# design.net
KiCad netlist of a schematic drawn in EasyEDA Pro
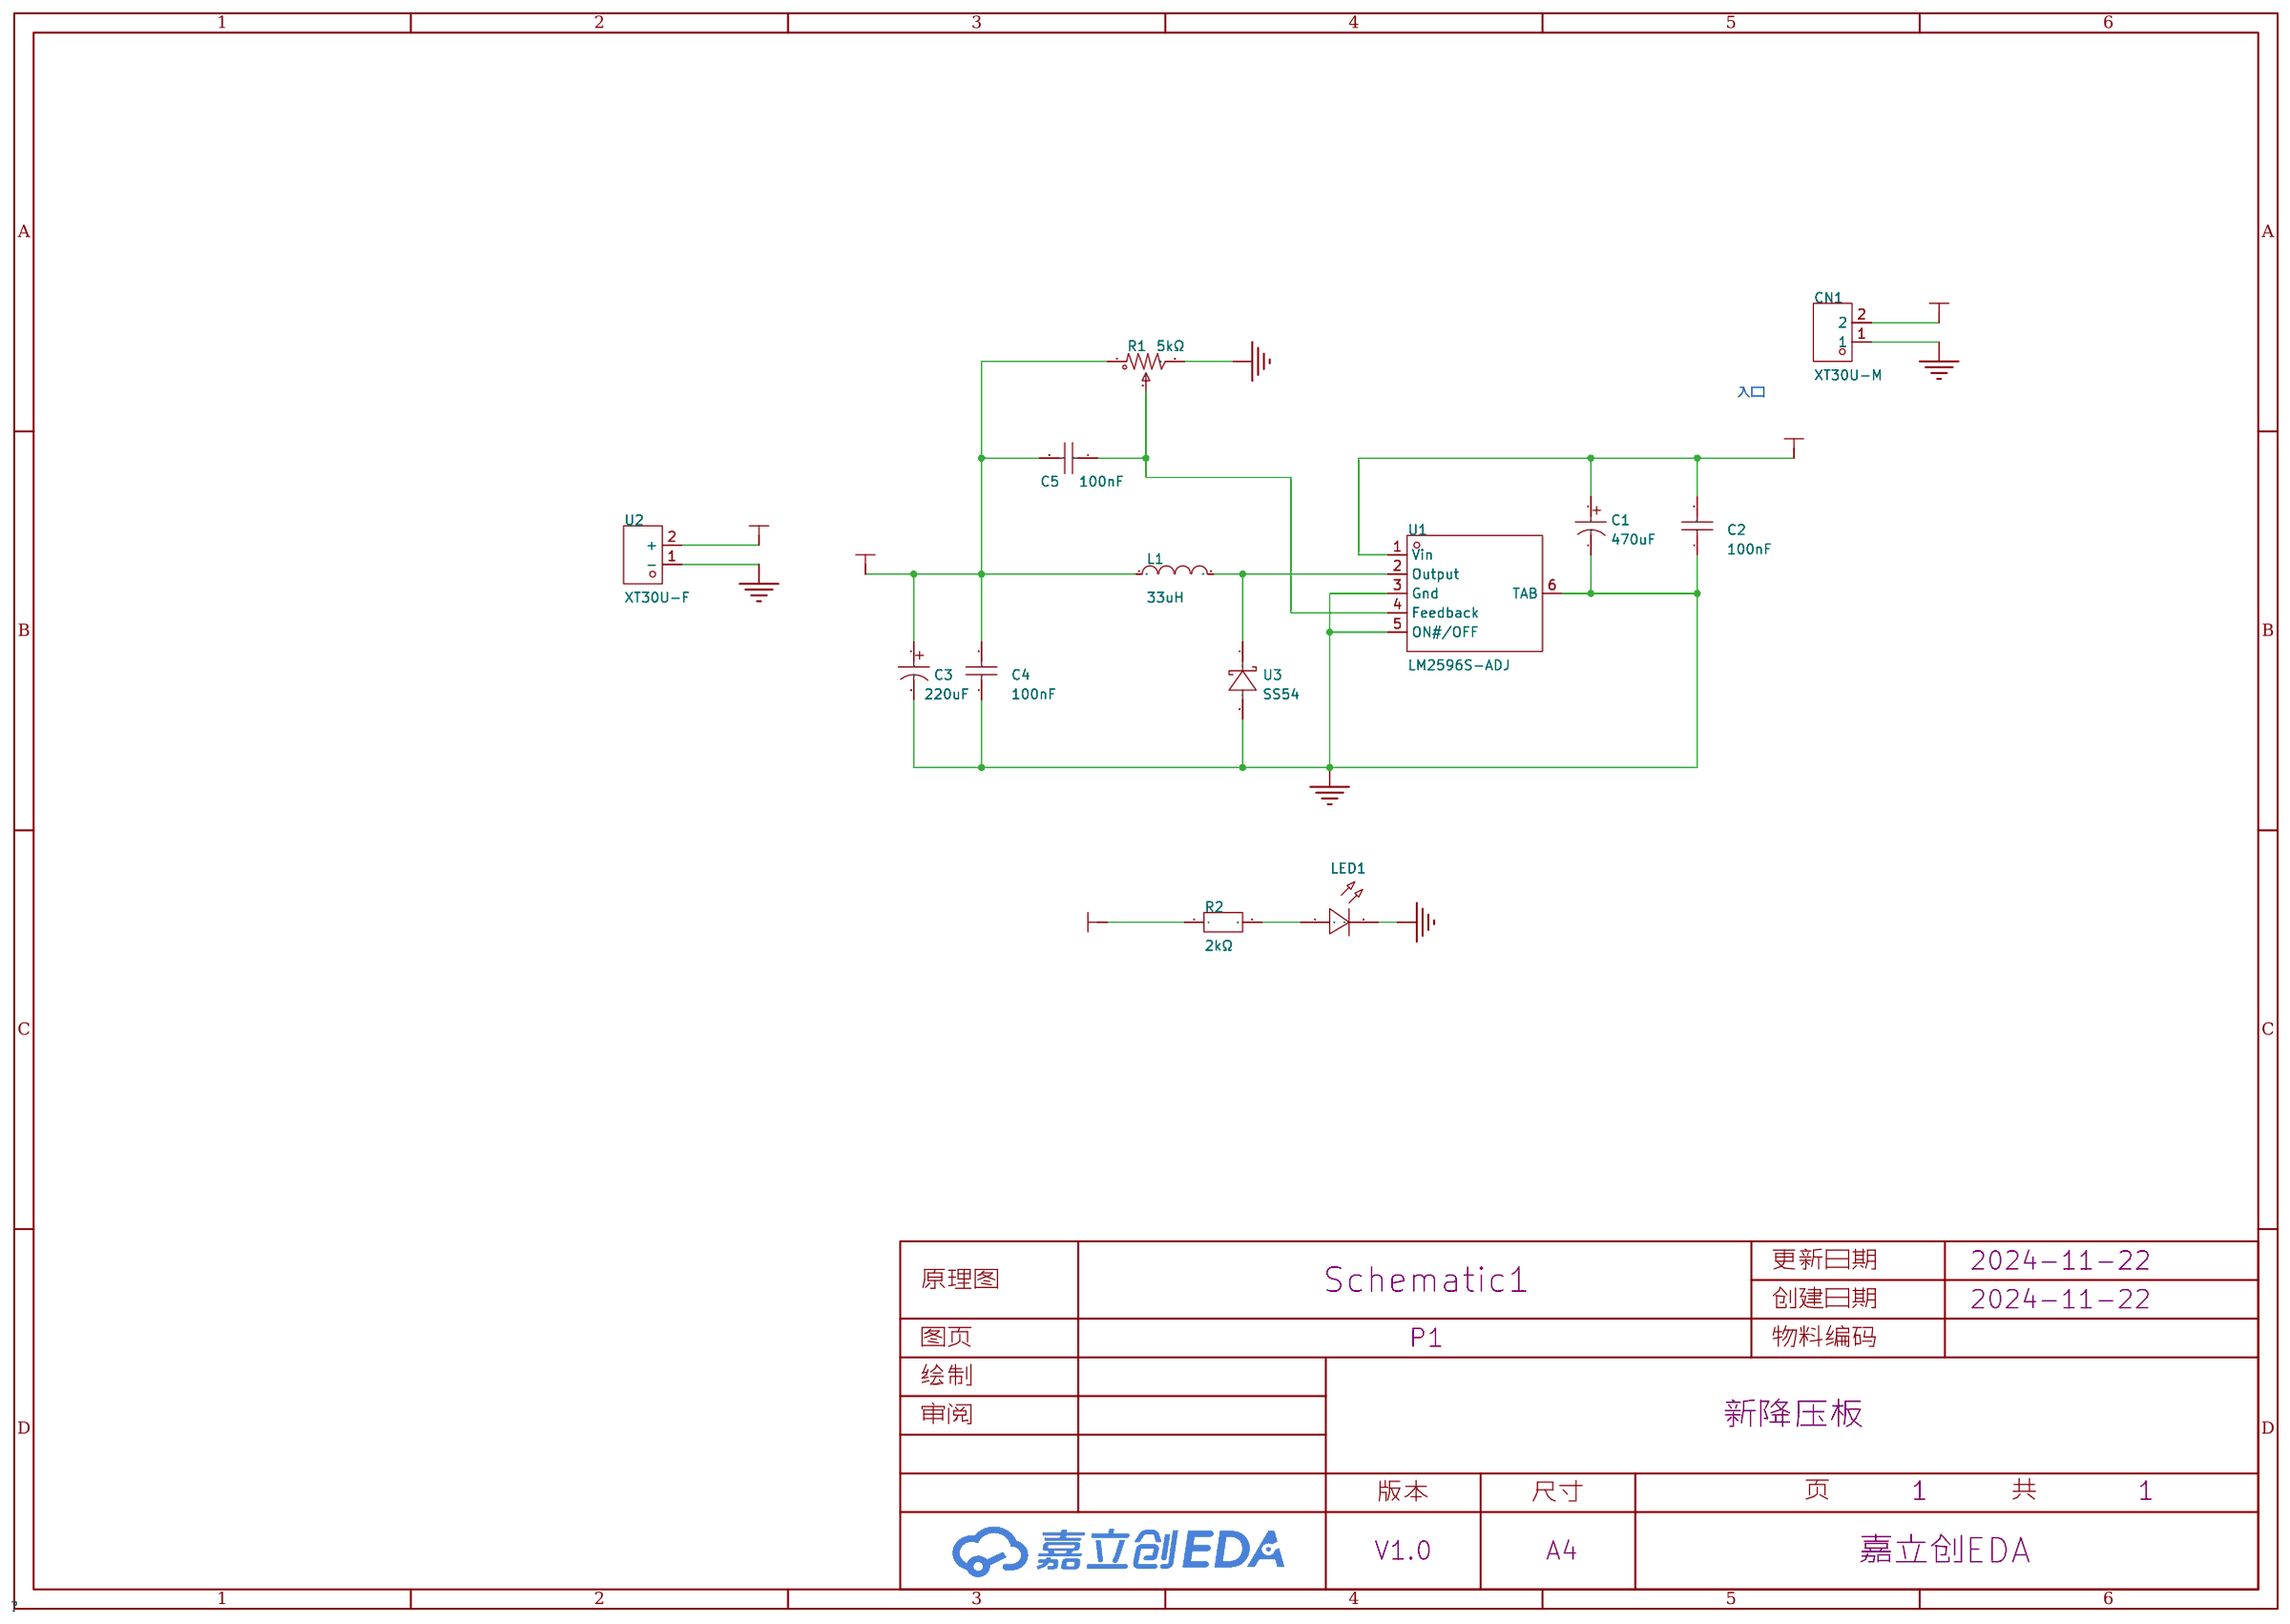
[diagram p0: schematic sheet]

(export (version "E")
  (design (tool "Eeschema 10.0.6"))
  (components
    (comp (ref "C1")
      (value "470uF")
      (footprint "easyedapro:CAP-SMD_BD8.0-L8.3-W8.3-FD")
      (description "容值:470uF;精度:±20%;额定电压:16V;纹波电流:450mA@120Hz;等效串联电阻:430mΩ;")
      (fields (field (name "Manufacturer Part") "RVE1C471M0810") (field (name "Manufacturer") "ROQANG(容强)"))
      (libsource (lib "easyedapro") (part "RVE1C471M0810"))
    )
    (comp (ref "C2")
      (value "100nF")
      (footprint "easyedapro:C0805")
      (description "容值:100nF;精度:±10%;额定电压:50V;材质(温度系数):X7R;")
      (fields
        (field (name "Manufacturer Part") "CL21B104KBCNNNC")
        (field (name "Manufacturer") "SAMSUNG(三星)")
      )
      (libsource (lib "easyedapro") (part "CL21B104KBCNNNC"))
    )
    (comp (ref "C3")
      (value "220uF")
      (footprint "easyedapro:CAP-SMD_BD6.3-L6.6-W6.6-FD")
      (description "容值:220uF;精度:±20%;额定电压:16V;纹波电流:110mA@120Hz;等效串联电阻:-;")
      (fields (field (name "Manufacturer Part") "VT1C221M0607") (field (name "Manufacturer") "ROQANG(容强)"))
      (libsource (lib "easyedapro") (part "VT1C221M0607"))
    )
    (comp (ref "C4")
      (value "100nF")
      (footprint "easyedapro:C0805")
      (description "容值:100nF;精度:±10%;额定电压:50V;材质(温度系数):X7R;")
      (fields
        (field (name "Manufacturer Part") "CL21B104KBCNNNC")
        (field (name "Manufacturer") "SAMSUNG(三星)")
      )
      (libsource (lib "easyedapro") (part "CL21B104KBCNNNC"))
    )
    (comp (ref "C5")
      (value "100nF")
      (footprint "easyedapro:C0805")
      (description "容值:100nF;精度:±10%;额定电压:50V;材质(温度系数):X7R;")
      (fields
        (field (name "Manufacturer Part") "CL21B104KBCNNNC")
        (field (name "Manufacturer") "SAMSUNG(三星)")
      )
      (libsource (lib "easyedapro") (part "CL21B104KBCNNNC"))
    )
    (comp (ref "CN1")
      (value "XT30U-M")
      (footprint "easyedapro:CONN-TH_XT30U-M")
      (description "类别:-;类型1:-;")
      (fields (field (name "Manufacturer") "AMASS(艾迈斯)"))
      (libsource (lib "easyedapro") (part "XT30U-M"))
    )
    (comp (ref "L1")
      (value "33uH")
      (footprint "easyedapro:IND-SMD_L12.0-W12.0")
      (description "电感值:33uH;精度:±20%;额定电流:3A;")
      (fields
        (field (name "Manufacturer Part") "SLH1207S330MTT")
        (field (name "Manufacturer") "Sunltech(韩国顺磁)")
      )
      (libsource (lib "easyedapro") (part "SLH1207S330MTT"))
    )
    (comp (ref "LED1")
      (value "~")
      (footprint "easyedapro:LED-TH_5mm")
      (libsource (lib "easyedapro") (part "LED_TH-R"))
    )
    (comp (ref "R1")
      (value "5kΩ")
      (footprint "easyedapro:RES-ADJ-TH_3P-L9.5-W4.85-P2.50-BL-BS")
      (description "阻值:5kΩ;精度:±10%;")
      (fields (field (name "Manufacturer Part") "3296W-1-502") (field (name "Manufacturer") "BOCHEN(博晨)"))
      (libsource (lib "easyedapro") (part "3296W-1-502"))
    )
    (comp (ref "R2")
      (value "2kΩ")
      (footprint "easyedapro:R0603")
      (description "阻值:2kΩ;精度:±1%;功率:-;温度系数:±100ppm/°C;")
      (fields
        (field (name "Manufacturer Part") "SC0603F2001F2BNRH")
        (field (name "Manufacturer") "Sunway(信维通信)")
      )
      (libsource (lib "easyedapro") (part "SC0603F2001F2BNRH"))
    )
    (comp (ref "U1")
      (value "LM2596S-ADJ")
      (footprint "easyedapro:TO-263-5_L10.2-W8.9-P1.70-BR")
      (description "功能类型:降压型;输出类型:可调;输入电压:40V;输出电压:1.2V~37V;输出电流:3A;")
      (fields (field (name "Manufacturer") "UMW(友台半导体)"))
      (libsource (lib "easyedapro") (part "LM2596S-ADJ"))
    )
    (comp (ref "U2")
      (value "XT30U-F")
      (footprint "easyedapro:CONN-TH_XT30U-F")
      (description "类别:-;类型1:-;")
      (fields (field (name "Manufacturer") "AMASS(艾迈斯)"))
      (libsource (lib "easyedapro") (part "XT30U-F"))
    )
    (comp (ref "U3")
      (value "SS54")
      (footprint "easyedapro:SMA_L4.2-W2.6-LS5.1-RD")
      (libsource (lib "easyedapro") (part "SS54_C9900023219"))
    )
  )
  (nets
    (net (code "1") (name "3V3") (class "Default")
      (node (ref "C3") (pin "1") (pinfunction "1_1") (pintype "input"))
      (node (ref "C4") (pin "2") (pinfunction "2_2") (pintype "input"))
      (node (ref "C5") (pin "2") (pinfunction "2_2") (pintype "input"))
      (node (ref "L1") (pin "1") (pinfunction "1_1") (pintype "unspecified"))
      (node (ref "R1") (pin "1") (pinfunction "1_1") (pintype "unspecified"))
      (node (ref "R2") (pin "1") (pinfunction "1_1") (pintype "unspecified"))
      (node (ref "U2") (pin "2") (pinfunction "+_2") (pintype "unspecified"))
    )
    (net (code "2") (name "12V") (class "Default")
      (node (ref "C1") (pin "1") (pinfunction "1_1") (pintype "input"))
      (node (ref "C2") (pin "2") (pinfunction "2_2") (pintype "input"))
      (node (ref "CN1") (pin "2") (pinfunction "2_2") (pintype "unspecified"))
      (node (ref "U1") (pin "1") (pinfunction "Vin_1") (pintype "unspecified"))
    )
    (net (code "3") (name "GND") (class "Default")
      (node (ref "C1") (pin "2") (pinfunction "2_2") (pintype "input"))
      (node (ref "C2") (pin "1") (pinfunction "1_1") (pintype "input"))
      (node (ref "C3") (pin "2") (pinfunction "2_2") (pintype "input"))
      (node (ref "C4") (pin "1") (pinfunction "1_1") (pintype "input"))
      (node (ref "CN1") (pin "1") (pinfunction "1_1") (pintype "unspecified"))
      (node (ref "LED1") (pin "2") (pinfunction "A_2") (pintype "input"))
      (node (ref "R1") (pin "3") (pinfunction "3_3") (pintype "unspecified"))
      (node (ref "U1") (pin "3") (pinfunction "Gnd_3") (pintype "unspecified"))
      (node (ref "U1") (pin "5") (pinfunction "ON#/OFF_5") (pintype "unspecified"))
      (node (ref "U1") (pin "6") (pinfunction "TAB_6") (pintype "unspecified"))
      (node (ref "U2") (pin "1") (pinfunction "-_1") (pintype "unspecified"))
      (node (ref "U3") (pin "2") (pinfunction "A_2") (pintype "unspecified"))
    )
    (net (code "4") (name "Net-(LED1-C)") (class "Default")
      (node (ref "LED1") (pin "1") (pinfunction "C_1") (pintype "input"))
      (node (ref "R2") (pin "2") (pinfunction "2_2") (pintype "unspecified"))
    )
    (net (code "5") (name "Net-(U1-Feedback)") (class "Default")
      (node (ref "C5") (pin "1") (pinfunction "1_1") (pintype "input"))
      (node (ref "R1") (pin "2") (pinfunction "2_2") (pintype "unspecified"))
      (node (ref "U1") (pin "4") (pinfunction "Feedback_4") (pintype "unspecified"))
    )
    (net (code "6") (name "Net-(U1-Output)") (class "Default")
      (node (ref "L1") (pin "2") (pinfunction "2_2") (pintype "unspecified"))
      (node (ref "U1") (pin "2") (pinfunction "Output_2") (pintype "unspecified"))
      (node (ref "U3") (pin "1") (pinfunction "C_1") (pintype "unspecified"))
    )
  )
)
